# HUD.net
KiCad netlist of a schematic drawn in Altium Designer
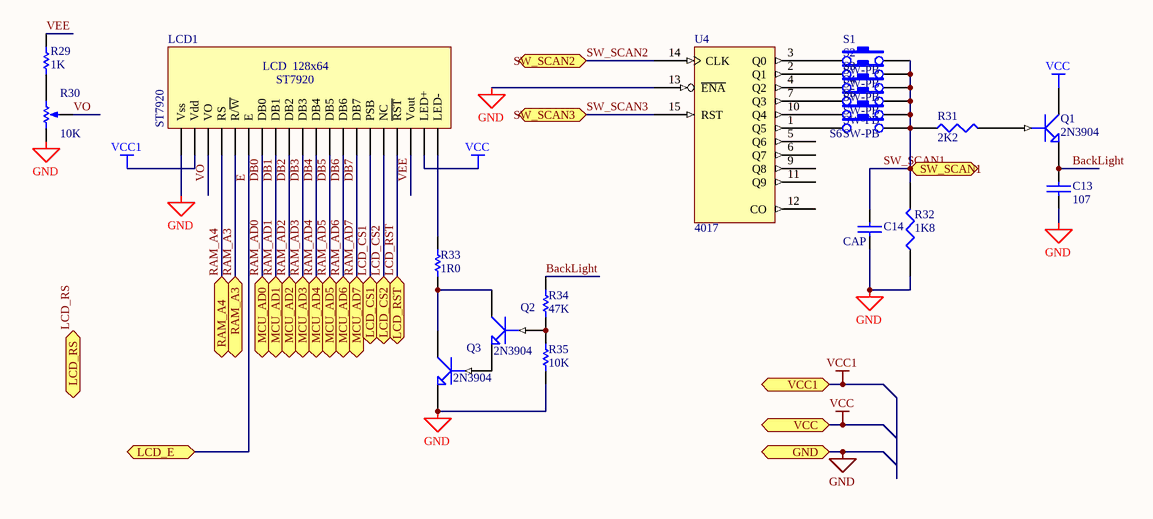
[diagram p0: HUD.SchDoc]

(export (version "E")
  (design (tool "Eeschema 10.0.6"))
  (components
    (comp (ref "C13")
      (value "107")
      (footprint "CAPMP7343X310N")
      (description "Capacitor")
      (libsource (lib "*") (part "CAP"))
    )
    (comp (ref "C14")
      (value "CAP")
      (footprint "C6-0805_N")
      (description "Capacitor")
      (libsource (lib "*") (part "CAP"))
    )
    (comp (ref "LCD1")
      (value "ST7920")
      (footprint "LCD12864B")
      (description "ST7920 LCD128X64")
      (libsource (lib "Schlib1") (part "ST7920"))
    )
    (comp (ref "Q1")
      (value "2N3904")
      (footprint "SOT23-3")
      (description "NPN Transistor")
      (libsource (lib "*") (part "NPN1"))
    )
    (comp (ref "Q2")
      (value "2N3904")
      (footprint "SOT23-3")
      (description "NPN Transistor")
      (libsource (lib "*") (part "NPN1"))
    )
    (comp (ref "Q3")
      (value "2N3904")
      (footprint "SOT23-3")
      (description "NPN Transistor")
      (libsource (lib "*") (part "NPN1"))
    )
    (comp (ref "R29")
      (value "1K")
      (footprint "6-0805_N")
      (description "Semiconductor Resistor")
      (fields (field (name "PUBLISHER") "Altium Limited"))
      (libsource (lib "*") (part "Res Semi"))
    )
    (comp (ref "R30")
      (value "10K")
      (footprint "BTXANH")
      (description "Potentiometer")
      (fields (field (name "PUBLISHER") "*"))
      (libsource (lib "*") (part "RPot"))
    )
    (comp (ref "R31") (value "2K2") (footprint "6-0805_N") (libsource (lib "*") (part "RES1")))
    (comp (ref "R32") (value "1K8") (footprint "6-0805_N") (libsource (lib "*") (part "RES1")))
    (comp (ref "R33")
      (value "1R0")
      (footprint "6-0805_N")
      (description "Semiconductor Resistor")
      (fields (field (name "PUBLISHER") "Altium Limited"))
      (libsource (lib "*") (part "Res Semi"))
    )
    (comp (ref "R34")
      (value "47K")
      (footprint "6-0805_N")
      (description "Semiconductor Resistor")
      (fields (field (name "PUBLISHER") "Altium Limited"))
      (libsource (lib "*") (part "Res Semi"))
    )
    (comp (ref "R35")
      (value "10K")
      (footprint "6-0805_N")
      (description "Semiconductor Resistor")
      (fields (field (name "PUBLISHER") "Altium Limited"))
      (libsource (lib "*") (part "Res Semi"))
    )
    (comp (ref "S1") (value "SW-PB") (footprint "CTCHIP_TO") (libsource (lib "*") (part "SW-PB")))
    (comp (ref "S2") (value "SW-PB") (footprint "CTCHIP_TO") (libsource (lib "*") (part "SW-PB")))
    (comp (ref "S3") (value "SW-PB") (footprint "CTCHIP_TO") (libsource (lib "*") (part "SW-PB")))
    (comp (ref "S4") (value "SW-PB") (footprint "CTCHIP_TO") (libsource (lib "*") (part "SW-PB")))
    (comp (ref "S5") (value "SW-PB") (footprint "CTCHIP_TO") (libsource (lib "*") (part "SW-PB")))
    (comp (ref "S6") (value "SW-PB") (footprint "CTCHIP_TO") (libsource (lib "*") (part "SW-PB")))
    (comp (ref "U4") (value "4017") (footprint "SOIC127P600X175-16AN") (libsource (lib "*") (part "4017")))
  )
  (nets
    (net (code "1") (name "/BackLight") (class "Default")
      (node (ref "C13") (pin "1") (pinfunction "1_1") (pintype "passive"))
      (node (ref "Q1") (pin "2") (pinfunction "E_2") (pintype "passive"))
      (node (ref "R34") (pin "2") (pinfunction "2_2") (pintype "passive"))
    )
    (net (code "2") (name "/DB0") (class "Default")
      (node (ref "LCD1") (pin "7") (pinfunction "DB0_7") (pintype "passive"))
    )
    (net (code "3") (name "/DB1") (class "Default")
      (node (ref "LCD1") (pin "8") (pinfunction "DB1_8") (pintype "passive"))
    )
    (net (code "4") (name "/DB2") (class "Default")
      (node (ref "LCD1") (pin "9") (pinfunction "DB2_9") (pintype "passive"))
    )
    (net (code "5") (name "/DB3") (class "Default")
      (node (ref "LCD1") (pin "10") (pinfunction "DB3_10") (pintype "passive"))
    )
    (net (code "6") (name "/DB4") (class "Default")
      (node (ref "LCD1") (pin "11") (pinfunction "DB4_11") (pintype "passive"))
    )
    (net (code "7") (name "/DB5") (class "Default")
      (node (ref "LCD1") (pin "12") (pinfunction "DB5_12") (pintype "passive"))
    )
    (net (code "8") (name "/DB6") (class "Default")
      (node (ref "LCD1") (pin "13") (pinfunction "DB6_13") (pintype "passive"))
    )
    (net (code "9") (name "/DB7") (class "Default")
      (node (ref "LCD1") (pin "14") (pinfunction "DB7_14") (pintype "passive"))
    )
    (net (code "10") (name "/E") (class "Default")
      (node (ref "LCD1") (pin "6") (pinfunction "E_6") (pintype "passive"))
    )
    (net (code "11") (name "/LCD_CS1") (class "Default")
      (node (ref "LCD1") (pin "15") (pinfunction "PSB_15") (pintype "passive"))
    )
    (net (code "12") (name "/LCD_CS2") (class "Default")
      (node (ref "LCD1") (pin "16") (pinfunction "NC_16") (pintype "passive"))
    )
    (net (code "14") (name "/LCD_RST") (class "Default")
      (node (ref "LCD1") (pin "17") (pinfunction "~{RST}_17") (pintype "passive"))
    )
    (net (code "15") (name "/RAM_A3") (class "Default")
      (node (ref "LCD1") (pin "5") (pinfunction "R/~{W}_5") (pintype "passive"))
    )
    (net (code "16") (name "/RAM_A4") (class "Default")
      (node (ref "LCD1") (pin "4") (pinfunction "RS_4") (pintype "passive"))
    )
    (net (code "17") (name "/SW_SCAN1") (class "Default")
      (node (ref "C14") (pin "1") (pinfunction "1_1") (pintype "passive"))
      (node (ref "R31") (pin "1") (pinfunction "1_1") (pintype "passive"))
      (node (ref "R32") (pin "2") (pinfunction "2_2") (pintype "passive"))
      (node (ref "S1") (pin "2") (pinfunction "2_2") (pintype "passive"))
      (node (ref "S2") (pin "2") (pinfunction "2_2") (pintype "passive"))
      (node (ref "S3") (pin "2") (pinfunction "2_2") (pintype "passive"))
      (node (ref "S4") (pin "2") (pinfunction "2_2") (pintype "passive"))
      (node (ref "S5") (pin "2") (pinfunction "2_2") (pintype "passive"))
      (node (ref "S6") (pin "2") (pinfunction "2_2") (pintype "passive"))
    )
    (net (code "18") (name "/SW_SCAN2") (class "Default")
      (node (ref "U4") (pin "14") (pinfunction "CLK_14") (pintype "input"))
    )
    (net (code "19") (name "/SW_SCAN3") (class "Default")
      (node (ref "U4") (pin "15") (pinfunction "RST_15") (pintype "input"))
    )
    (net (code "20") (name "/VEE") (class "Default")
      (node (ref "LCD1") (pin "18") (pinfunction "Vout_18") (pintype "passive"))
      (node (ref "R29") (pin "2") (pinfunction "2_2") (pintype "passive"))
    )
    (net (code "21") (name "/VO") (class "Default")
      (node (ref "LCD1") (pin "3") (pinfunction "VO_3") (pintype "passive"))
      (node (ref "R30") (pin "2") (pinfunction "TAP_2") (pintype "passive"))
    )
    (net (code "22") (name "GND") (class "Default")
      (node (ref "C13") (pin "2") (pinfunction "2_2") (pintype "passive"))
      (node (ref "C14") (pin "2") (pinfunction "2_2") (pintype "passive"))
      (node (ref "LCD1") (pin "1") (pinfunction "Vss_1") (pintype "passive"))
      (node (ref "Q3") (pin "2") (pinfunction "E_2") (pintype "passive"))
      (node (ref "R30") (pin "1") (pinfunction "TOP_1") (pintype "passive"))
      (node (ref "R32") (pin "1") (pinfunction "1_1") (pintype "passive"))
      (node (ref "R35") (pin "1") (pinfunction "1_1") (pintype "passive"))
      (node (ref "U4") (pin "13") (pinfunction "~{ENA}_13") (pintype "input"))
      (node (ref "U4") (pin "8") (pinfunction "GND_8") (pintype "power_in"))
    )
    (net (code "23") (name "Net-(LCD1-LED-)") (class "Default")
      (node (ref "LCD1") (pin "20") (pinfunction "LED-_20") (pintype "passive"))
      (node (ref "R33") (pin "2") (pinfunction "2_2") (pintype "passive"))
    )
    (net (code "24") (name "Net-(Q1-B)") (class "Default")
      (node (ref "Q1") (pin "1") (pinfunction "B_1") (pintype "input"))
      (node (ref "R31") (pin "2") (pinfunction "2_2") (pintype "passive"))
    )
    (net (code "25") (name "Net-(Q2-B)") (class "Default")
      (node (ref "Q2") (pin "1") (pinfunction "B_1") (pintype "input"))
      (node (ref "R34") (pin "1") (pinfunction "1_1") (pintype "passive"))
      (node (ref "R35") (pin "2") (pinfunction "2_2") (pintype "passive"))
    )
    (net (code "26") (name "Net-(Q2-C)") (class "Default")
      (node (ref "Q2") (pin "3") (pinfunction "C_3") (pintype "passive"))
      (node (ref "Q3") (pin "3") (pinfunction "C_3") (pintype "passive"))
      (node (ref "R33") (pin "1") (pinfunction "1_1") (pintype "passive"))
    )
    (net (code "27") (name "Net-(Q2-E)") (class "Default")
      (node (ref "Q2") (pin "2") (pinfunction "E_2") (pintype "passive"))
      (node (ref "Q3") (pin "1") (pinfunction "B_1") (pintype "input"))
    )
    (net (code "28") (name "Net-(R30-BOT)") (class "Default")
      (node (ref "R29") (pin "1") (pinfunction "1_1") (pintype "passive"))
      (node (ref "R30") (pin "3") (pinfunction "BOT_3") (pintype "passive"))
    )
    (net (code "29") (name "Net-(U4-Q0)") (class "Default")
      (node (ref "S1") (pin "1") (pinfunction "1_1") (pintype "passive"))
      (node (ref "U4") (pin "3") (pinfunction "Q0_3") (pintype "output"))
    )
    (net (code "30") (name "Net-(U4-Q1)") (class "Default")
      (node (ref "S2") (pin "1") (pinfunction "1_1") (pintype "passive"))
      (node (ref "U4") (pin "2") (pinfunction "Q1_2") (pintype "output"))
    )
    (net (code "31") (name "Net-(U4-Q2)") (class "Default")
      (node (ref "S3") (pin "1") (pinfunction "1_1") (pintype "passive"))
      (node (ref "U4") (pin "4") (pinfunction "Q2_4") (pintype "output"))
    )
    (net (code "32") (name "Net-(U4-Q3)") (class "Default")
      (node (ref "S4") (pin "1") (pinfunction "1_1") (pintype "passive"))
      (node (ref "U4") (pin "7") (pinfunction "Q3_7") (pintype "output"))
    )
    (net (code "33") (name "Net-(U4-Q4)") (class "Default")
      (node (ref "S5") (pin "1") (pinfunction "1_1") (pintype "passive"))
      (node (ref "U4") (pin "10") (pinfunction "Q4_10") (pintype "output"))
    )
    (net (code "34") (name "Net-(U4-Q5)") (class "Default")
      (node (ref "S6") (pin "1") (pinfunction "1_1") (pintype "passive"))
      (node (ref "U4") (pin "1") (pinfunction "Q5_1") (pintype "output"))
    )
    (net (code "35") (name "VCC") (class "Default")
      (node (ref "LCD1") (pin "19") (pinfunction "LED+_19") (pintype "passive"))
      (node (ref "Q1") (pin "3") (pinfunction "C_3") (pintype "passive"))
      (node (ref "U4") (pin "16") (pinfunction "VCC_16") (pintype "power_in"))
    )
    (net (code "36") (name "VCC1") (class "Default")
      (node (ref "LCD1") (pin "2") (pinfunction "Vdd_2") (pintype "passive"))
    )
    (net (code "37") (name "unconnected-(U4-CO-Pad12)") (class "Default")
      (node (ref "U4") (pin "12") (pinfunction "CO_12") (pintype "output"))
    )
    (net (code "38") (name "unconnected-(U4-Q6-Pad5)") (class "Default")
      (node (ref "U4") (pin "5") (pinfunction "Q6_5") (pintype "output"))
    )
    (net (code "39") (name "unconnected-(U4-Q7-Pad6)") (class "Default")
      (node (ref "U4") (pin "6") (pinfunction "Q7_6") (pintype "output"))
    )
    (net (code "40") (name "unconnected-(U4-Q8-Pad9)") (class "Default")
      (node (ref "U4") (pin "9") (pinfunction "Q8_9") (pintype "output"))
    )
    (net (code "41") (name "unconnected-(U4-Q9-Pad11)") (class "Default")
      (node (ref "U4") (pin "11") (pinfunction "Q9_11") (pintype "output"))
    )
  )
)
